# PzemBoard.net
KiCad netlist of a schematic drawn in EAGLE
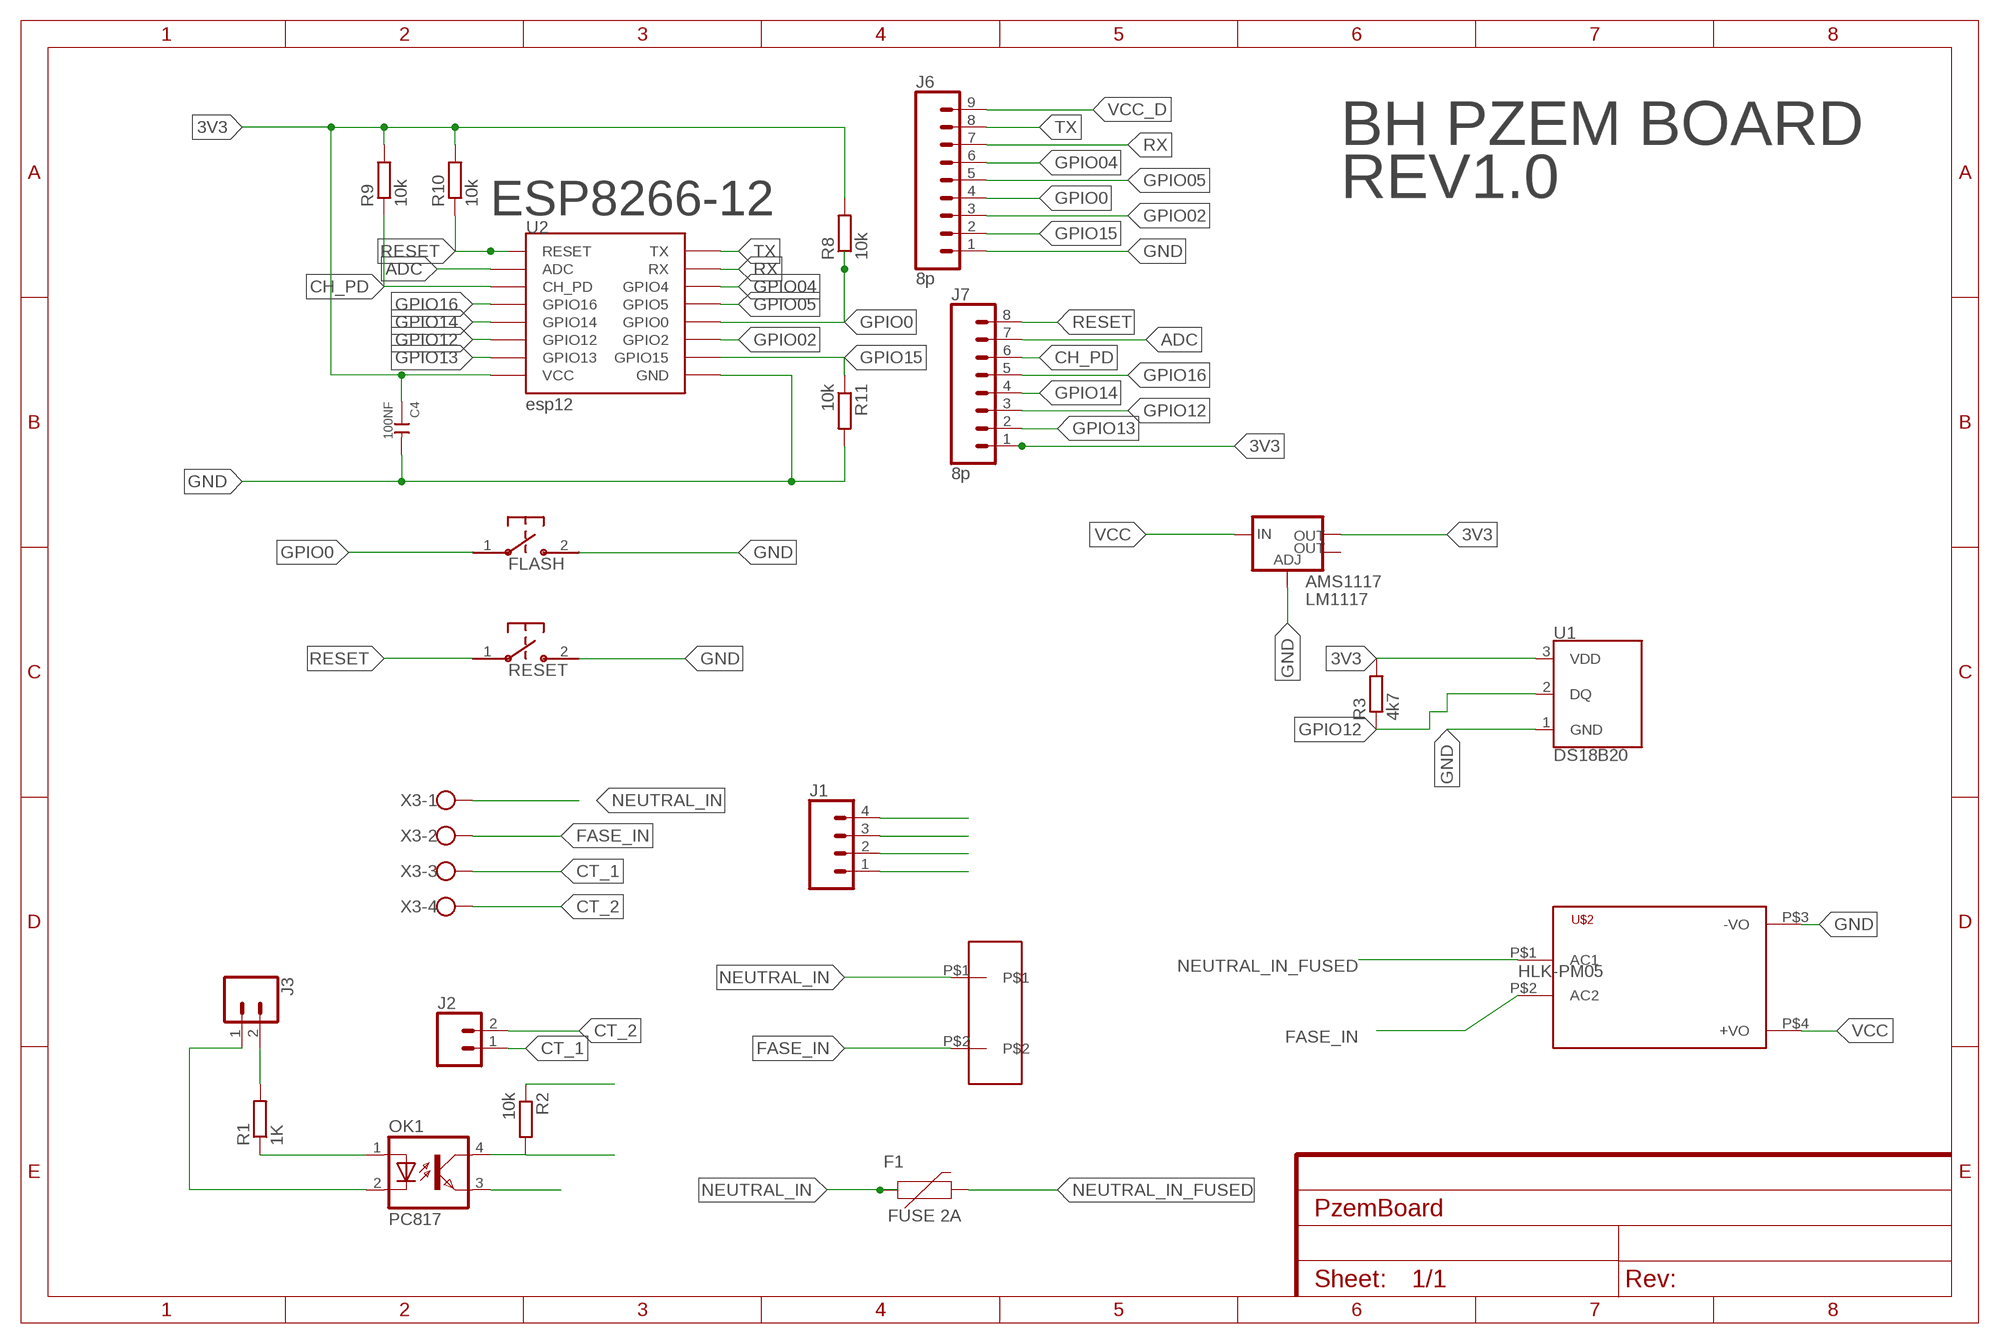
[diagram p0: schematic, sheet 1]

(export (version "E")
  (design (tool "Eeschema 10.0.6"))
  (components
    (comp (ref "AMS1117")
      (value "LM1117")
      (footprint "eagle-import:SOT223")
      (libsource (lib "eagle-import") (part "V_REG_LM1117SOT223"))
    )
    (comp (ref "C4")
      (value "100NF")
      (footprint "eagle-import:C1206")
      (fields (field (name "MPN") "CC1206KKX7RCBB102"))
      (libsource (lib "eagle-import") (part "CERAMIC-1NF-1KV-10%-X7R?(1206)"))
    )
    (comp (ref "F1")
      (value "FUSE 2A")
      (footprint "eagle-import:PTH")
      (libsource (lib "eagle-import") (part "PPTC_PTH"))
    )
    (comp (ref "FLASH")
      (value "B3U-1000P-2P-SMD")
      (footprint "eagle-import:B3U-1000P")
      (fields
        (field (name "MANUFACTURER") "Omron")
        (field (name "MPN") "B3U-1000P")
        (field (name "SPICEPREFIX") "F")
      )
      (libsource (lib "eagle-import") (part "B3U-1000P"))
    )
    (comp (ref "J1")
      (value "CONN_04")
      (footprint "eagle-import:1X04")
      (libsource (lib "eagle-import") (part "CONN_04"))
    )
    (comp (ref "J2")
      (value "CONN_02")
      (footprint "eagle-import:1X02")
      (libsource (lib "eagle-import") (part "CONN_02"))
    )
    (comp (ref "J3")
      (value "CONN_02")
      (footprint "eagle-import:1X02")
      (libsource (lib "eagle-import") (part "CONN_02"))
    )
    (comp (ref "J6")
      (value "8p")
      (footprint "eagle-import:1X09")
      (libsource (lib "eagle-import") (part "CONN_09"))
    )
    (comp (ref "J7")
      (value "8p")
      (footprint "eagle-import:1X08")
      (libsource (lib "eagle-import") (part "CONN_08{dblquote}"))
    )
    (comp (ref "OK1")
      (value "PC817")
      (footprint "eagle-import:DIL04")
      (fields (field (name "MPN") "PC817X4J000F"))
      (libsource (lib "eagle-import") (part "PC817"))
    )
    (comp (ref "R1")
      (value "1K")
      (footprint "eagle-import:R0603")
      (libsource (lib "eagle-import") (part "R-EU_R0603"))
    )
    (comp (ref "R2")
      (value "10k")
      (footprint "eagle-import:R0603")
      (libsource (lib "eagle-import") (part "R-EU_R0603"))
    )
    (comp (ref "R3")
      (value "4k7")
      (footprint "eagle-import:R0603")
      (libsource (lib "eagle-import") (part "R-EU_R0603"))
    )
    (comp (ref "R8")
      (value "10k")
      (footprint "eagle-import:R0603")
      (libsource (lib "eagle-import") (part "R-EU_R0603"))
    )
    (comp (ref "R9")
      (value "10k")
      (footprint "eagle-import:R0603")
      (libsource (lib "eagle-import") (part "R-EU_R0603"))
    )
    (comp (ref "R10")
      (value "10k")
      (footprint "eagle-import:R0603")
      (libsource (lib "eagle-import") (part "R-EU_R0603"))
    )
    (comp (ref "R11")
      (value "10k")
      (footprint "eagle-import:R0603")
      (libsource (lib "eagle-import") (part "R-EU_R0603"))
    )
    (comp (ref "RESET")
      (value "B3U-1000P-2P-SMD")
      (footprint "eagle-import:B3U-1000P")
      (fields (field (name "MANUFACTURER") "Omron") (field (name "MPN") "B3U-1000P"))
      (libsource (lib "eagle-import") (part "B3U-1000P"))
    )
    (comp (ref "U$1")
      (value "SCREWTERMINALS_5MM_2")
      (footprint "eagle-import:TERMINAL_2X")
      (libsource (lib "eagle-import") (part "SCREWTERMINALS_5MM_2"))
    )
    (comp (ref "U$2")
      (value "HKLPM01")
      (footprint "eagle-import:HKLPM01")
      (libsource (lib "eagle-import") (part "HKLPM01"))
    )
    (comp (ref "U1")
      (value "DS18B20")
      (footprint "eagle-import:TO-92-AMMO")
      (libsource (lib "eagle-import") (part "DS18B20"))
    )
    (comp (ref "U2")
      (value "esp12")
      (footprint "eagle-import:ESP12-SMD")
      (libsource (lib "eagle-import") (part "ESP12SMD"))
    )
    (comp (ref "X3")
      (value "W237-4")
      (footprint "eagle-import:W237-4")
      (libsource (lib "eagle-import") (part "W237-4"))
    )
  )
  (nets
    (net (code "1") (name "3V3") (class "Default")
      (node (ref "AMS1117") (pin "2") (pinfunction "OUT_2") (pintype "output"))
      (node (ref "C4") (pin "1") (pinfunction "1_1") (pintype "passive"))
      (node (ref "J7") (pin "1") (pinfunction "1_1") (pintype "passive"))
      (node (ref "R10") (pin "2") (pinfunction "2_2") (pintype "passive"))
      (node (ref "R3") (pin "2") (pinfunction "2_2") (pintype "passive"))
      (node (ref "R8") (pin "2") (pinfunction "2_2") (pintype "passive"))
      (node (ref "R9") (pin "2") (pinfunction "2_2") (pintype "passive"))
      (node (ref "U1") (pin "3") (pinfunction "VDD_3") (pintype "power_in"))
      (node (ref "U2") (pin "VCC") (pinfunction "VCC_VCC") (pintype "bidirectional"))
    )
    (net (code "2") (name "ADC") (class "Default")
      (node (ref "J7") (pin "7") (pinfunction "7_7") (pintype "passive"))
      (node (ref "U2") (pin "ADC") (pinfunction "ADC_ADC") (pintype "bidirectional"))
    )
    (net (code "3") (name "CH_PD") (class "Default")
      (node (ref "J7") (pin "6") (pinfunction "6_6") (pintype "passive"))
      (node (ref "R9") (pin "1") (pinfunction "1_1") (pintype "passive"))
      (node (ref "U2") (pin "CH_PD") (pinfunction "CH_PD_CH_PD") (pintype "bidirectional"))
    )
    (net (code "4") (name "CT_1") (class "Default")
      (node (ref "J2") (pin "1") (pinfunction "1_1") (pintype "passive"))
      (node (ref "X3") (pin "3") (pinfunction "KL_3") (pintype "passive"))
    )
    (net (code "5") (name "CT_2") (class "Default")
      (node (ref "J2") (pin "2") (pinfunction "2_2") (pintype "passive"))
      (node (ref "X3") (pin "4") (pinfunction "KL_4") (pintype "passive"))
    )
    (net (code "6") (name "FASE_IN") (class "Default")
      (node (ref "U$1") (pin "P$2") (pinfunction "P$2_P$2") (pintype "bidirectional"))
      (node (ref "U$2") (pin "P$2") (pinfunction "AC2_P$2") (pintype "bidirectional"))
      (node (ref "X3") (pin "2") (pinfunction "KL_2") (pintype "passive"))
    )
    (net (code "7") (name "GND") (class "Default")
      (node (ref "AMS1117") (pin "1") (pinfunction "ADJ_1") (pintype "input"))
      (node (ref "C4") (pin "2") (pinfunction "2_2") (pintype "passive"))
      (node (ref "FLASH") (pin "2") (pinfunction "P$2_2") (pintype "passive"))
      (node (ref "J1") (pin "4") (pinfunction "4_4") (pintype "passive"))
      (node (ref "J6") (pin "1") (pinfunction "1_1") (pintype "passive"))
      (node (ref "OK1") (pin "3") (pinfunction "EMIT_3") (pintype "passive"))
      (node (ref "R11") (pin "2") (pinfunction "2_2") (pintype "passive"))
      (node (ref "RESET") (pin "2") (pinfunction "P$2_2") (pintype "passive"))
      (node (ref "U$2") (pin "P$3") (pinfunction "-VO_P$3") (pintype "bidirectional"))
      (node (ref "U1") (pin "1") (pinfunction "GND_1") (pintype "power_in"))
      (node (ref "U2") (pin "GND") (pinfunction "GND_GND") (pintype "bidirectional"))
    )
    (net (code "8") (name "GPIO0") (class "Default")
      (node (ref "FLASH") (pin "1") (pinfunction "P$1_1") (pintype "passive"))
      (node (ref "J6") (pin "4") (pinfunction "4_4") (pintype "passive"))
      (node (ref "R8") (pin "1") (pinfunction "1_1") (pintype "passive"))
      (node (ref "U2") (pin "GPIO0") (pinfunction "GPIO0_GPIO0") (pintype "bidirectional"))
    )
    (net (code "9") (name "GPIO02") (class "Default")
      (node (ref "J6") (pin "3") (pinfunction "3_3") (pintype "passive"))
      (node (ref "U2") (pin "GPIO2") (pinfunction "GPIO2_GPIO2") (pintype "bidirectional"))
    )
    (net (code "10") (name "GPIO04") (class "Default")
      (node (ref "J1") (pin "2") (pinfunction "2_2") (pintype "passive"))
      (node (ref "J6") (pin "6") (pinfunction "6_6") (pintype "passive"))
      (node (ref "U2") (pin "GPIO4") (pinfunction "GPIO4_GPIO4") (pintype "bidirectional"))
    )
    (net (code "11") (name "GPIO05") (class "Default")
      (node (ref "J1") (pin "3") (pinfunction "3_3") (pintype "passive"))
      (node (ref "J6") (pin "5") (pinfunction "5_5") (pintype "passive"))
      (node (ref "U2") (pin "GPIO5") (pinfunction "GPIO5_GPIO5") (pintype "bidirectional"))
    )
    (net (code "12") (name "GPIO12") (class "Default")
      (node (ref "J7") (pin "3") (pinfunction "3_3") (pintype "passive"))
      (node (ref "R3") (pin "1") (pinfunction "1_1") (pintype "passive"))
      (node (ref "U1") (pin "2") (pinfunction "DQ_2") (pintype "bidirectional"))
      (node (ref "U2") (pin "GPIO12") (pinfunction "GPIO12_GPIO12") (pintype "bidirectional"))
    )
    (net (code "13") (name "GPIO13") (class "Default")
      (node (ref "J7") (pin "2") (pinfunction "2_2") (pintype "passive"))
      (node (ref "U2") (pin "GPIO13") (pinfunction "GPIO13_GPIO13") (pintype "bidirectional"))
    )
    (net (code "14") (name "GPIO14") (class "Default")
      (node (ref "J7") (pin "4") (pinfunction "4_4") (pintype "passive"))
      (node (ref "OK1") (pin "4") (pinfunction "COL_4") (pintype "passive"))
      (node (ref "R2") (pin "2") (pinfunction "2_2") (pintype "passive"))
      (node (ref "U2") (pin "GPIO14") (pinfunction "GPIO14_GPIO14") (pintype "bidirectional"))
    )
    (net (code "15") (name "GPIO15") (class "Default")
      (node (ref "J6") (pin "2") (pinfunction "2_2") (pintype "passive"))
      (node (ref "R11") (pin "1") (pinfunction "1_1") (pintype "passive"))
      (node (ref "U2") (pin "GPIO15") (pinfunction "GPIO15_GPIO15") (pintype "bidirectional"))
    )
    (net (code "16") (name "GPIO16") (class "Default")
      (node (ref "J7") (pin "5") (pinfunction "5_5") (pintype "passive"))
      (node (ref "U2") (pin "GPIO16") (pinfunction "GPIO16_GPIO16") (pintype "bidirectional"))
    )
    (net (code "17") (name "NEUTRAL_IN") (class "Default")
      (node (ref "F1") (pin "P$1") (pinfunction "1_P$1") (pintype "bidirectional"))
      (node (ref "U$1") (pin "P$1") (pinfunction "P$1_P$1") (pintype "bidirectional"))
      (node (ref "X3") (pin "1") (pinfunction "KL_1") (pintype "passive"))
    )
    (net (code "18") (name "NEUTRAL_IN_FUSED") (class "Default")
      (node (ref "F1") (pin "P$2") (pinfunction "2_P$2") (pintype "bidirectional"))
      (node (ref "U$2") (pin "P$1") (pinfunction "AC1_P$1") (pintype "bidirectional"))
    )
    (net (code "19") (name "Net-(J3-Pad2)") (class "Default")
      (node (ref "J3") (pin "2") (pinfunction "2_2") (pintype "passive"))
      (node (ref "R1") (pin "2") (pinfunction "2_2") (pintype "passive"))
    )
    (net (code "20") (name "Net-(OK1-A)") (class "Default")
      (node (ref "OK1") (pin "1") (pinfunction "A_1") (pintype "passive"))
      (node (ref "R1") (pin "1") (pinfunction "1_1") (pintype "passive"))
    )
    (net (code "21") (name "Net-(OK1-C)") (class "Default")
      (node (ref "J3") (pin "1") (pinfunction "1_1") (pintype "passive"))
      (node (ref "OK1") (pin "2") (pinfunction "C_2") (pintype "passive"))
    )
    (net (code "22") (name "RESET") (class "Default")
      (node (ref "J7") (pin "8") (pinfunction "8_8") (pintype "passive"))
      (node (ref "R10") (pin "1") (pinfunction "1_1") (pintype "passive"))
      (node (ref "RESET") (pin "1") (pinfunction "P$1_1") (pintype "passive"))
      (node (ref "U2") (pin "RESET") (pinfunction "RESET_RESET") (pintype "bidirectional"))
    )
    (net (code "23") (name "RX") (class "Default")
      (node (ref "J6") (pin "7") (pinfunction "7_7") (pintype "passive"))
      (node (ref "U2") (pin "RXD0") (pinfunction "RX_RXD0") (pintype "bidirectional"))
    )
    (net (code "24") (name "TX") (class "Default")
      (node (ref "J6") (pin "8") (pinfunction "8_8") (pintype "passive"))
      (node (ref "U2") (pin "TXD0") (pinfunction "TX_TXD0") (pintype "bidirectional"))
    )
    (net (code "25") (name "VCC") (class "Default")
      (node (ref "AMS1117") (pin "3") (pinfunction "IN_3") (pintype "input"))
      (node (ref "R2") (pin "1") (pinfunction "1_1") (pintype "passive"))
      (node (ref "U$2") (pin "P$4") (pinfunction "+VO_P$4") (pintype "bidirectional"))
    )
    (net (code "26") (name "VCC_D") (class "Default")
      (node (ref "J1") (pin "1") (pinfunction "1_1") (pintype "passive"))
      (node (ref "J6") (pin "9") (pinfunction "9_9") (pintype "passive"))
    )
    (net (code "27") (name "unconnected-(AMS1117-OUT-Pad4)") (class "Default")
      (node (ref "AMS1117") (pin "4") (pinfunction "OUT_4") (pintype "output"))
    )
  )
)
